# board.net
KiCad netlist of a schematic drawn in EAGLE
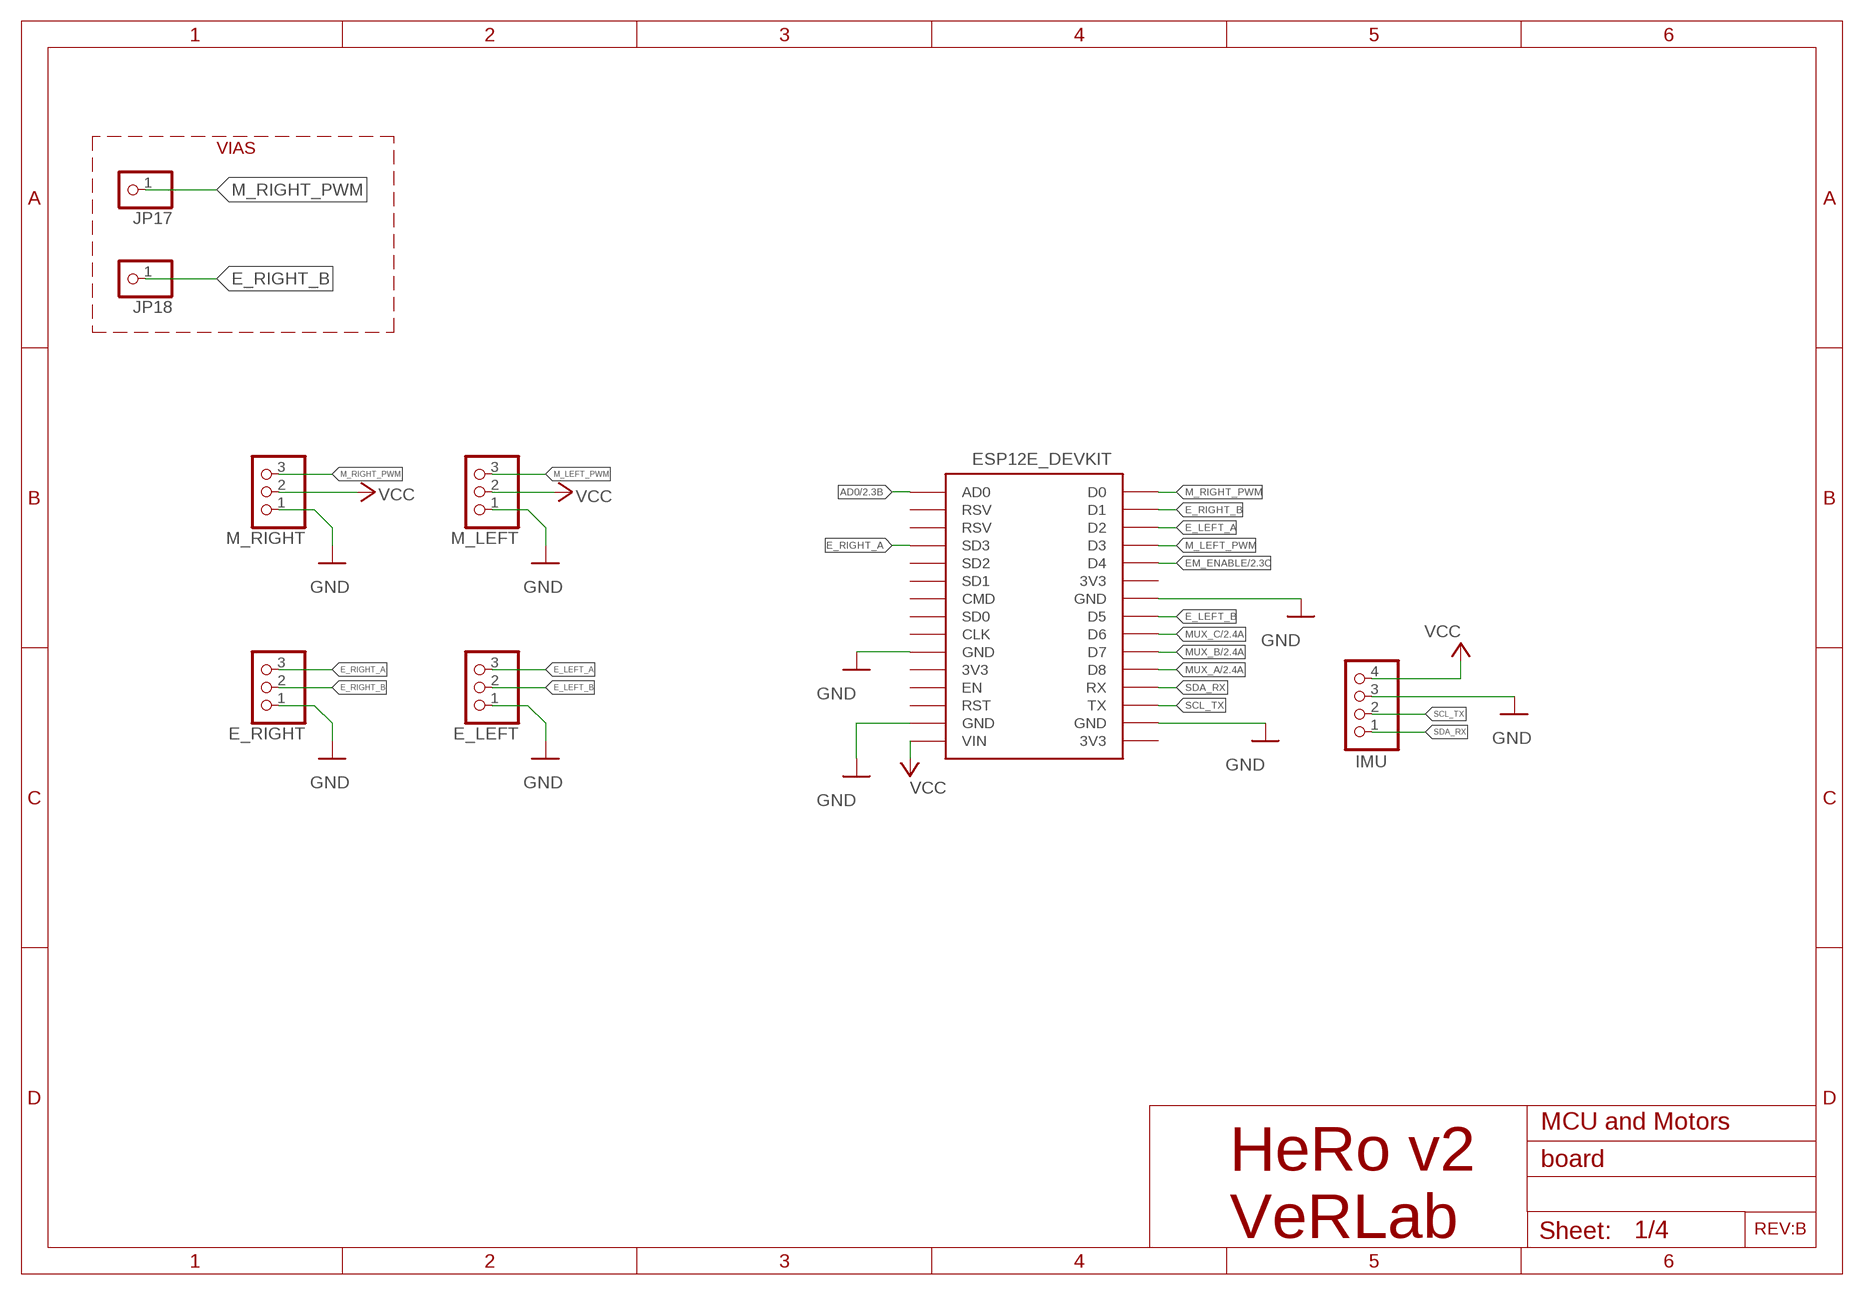
[diagram p0: schematic, sheet 1]
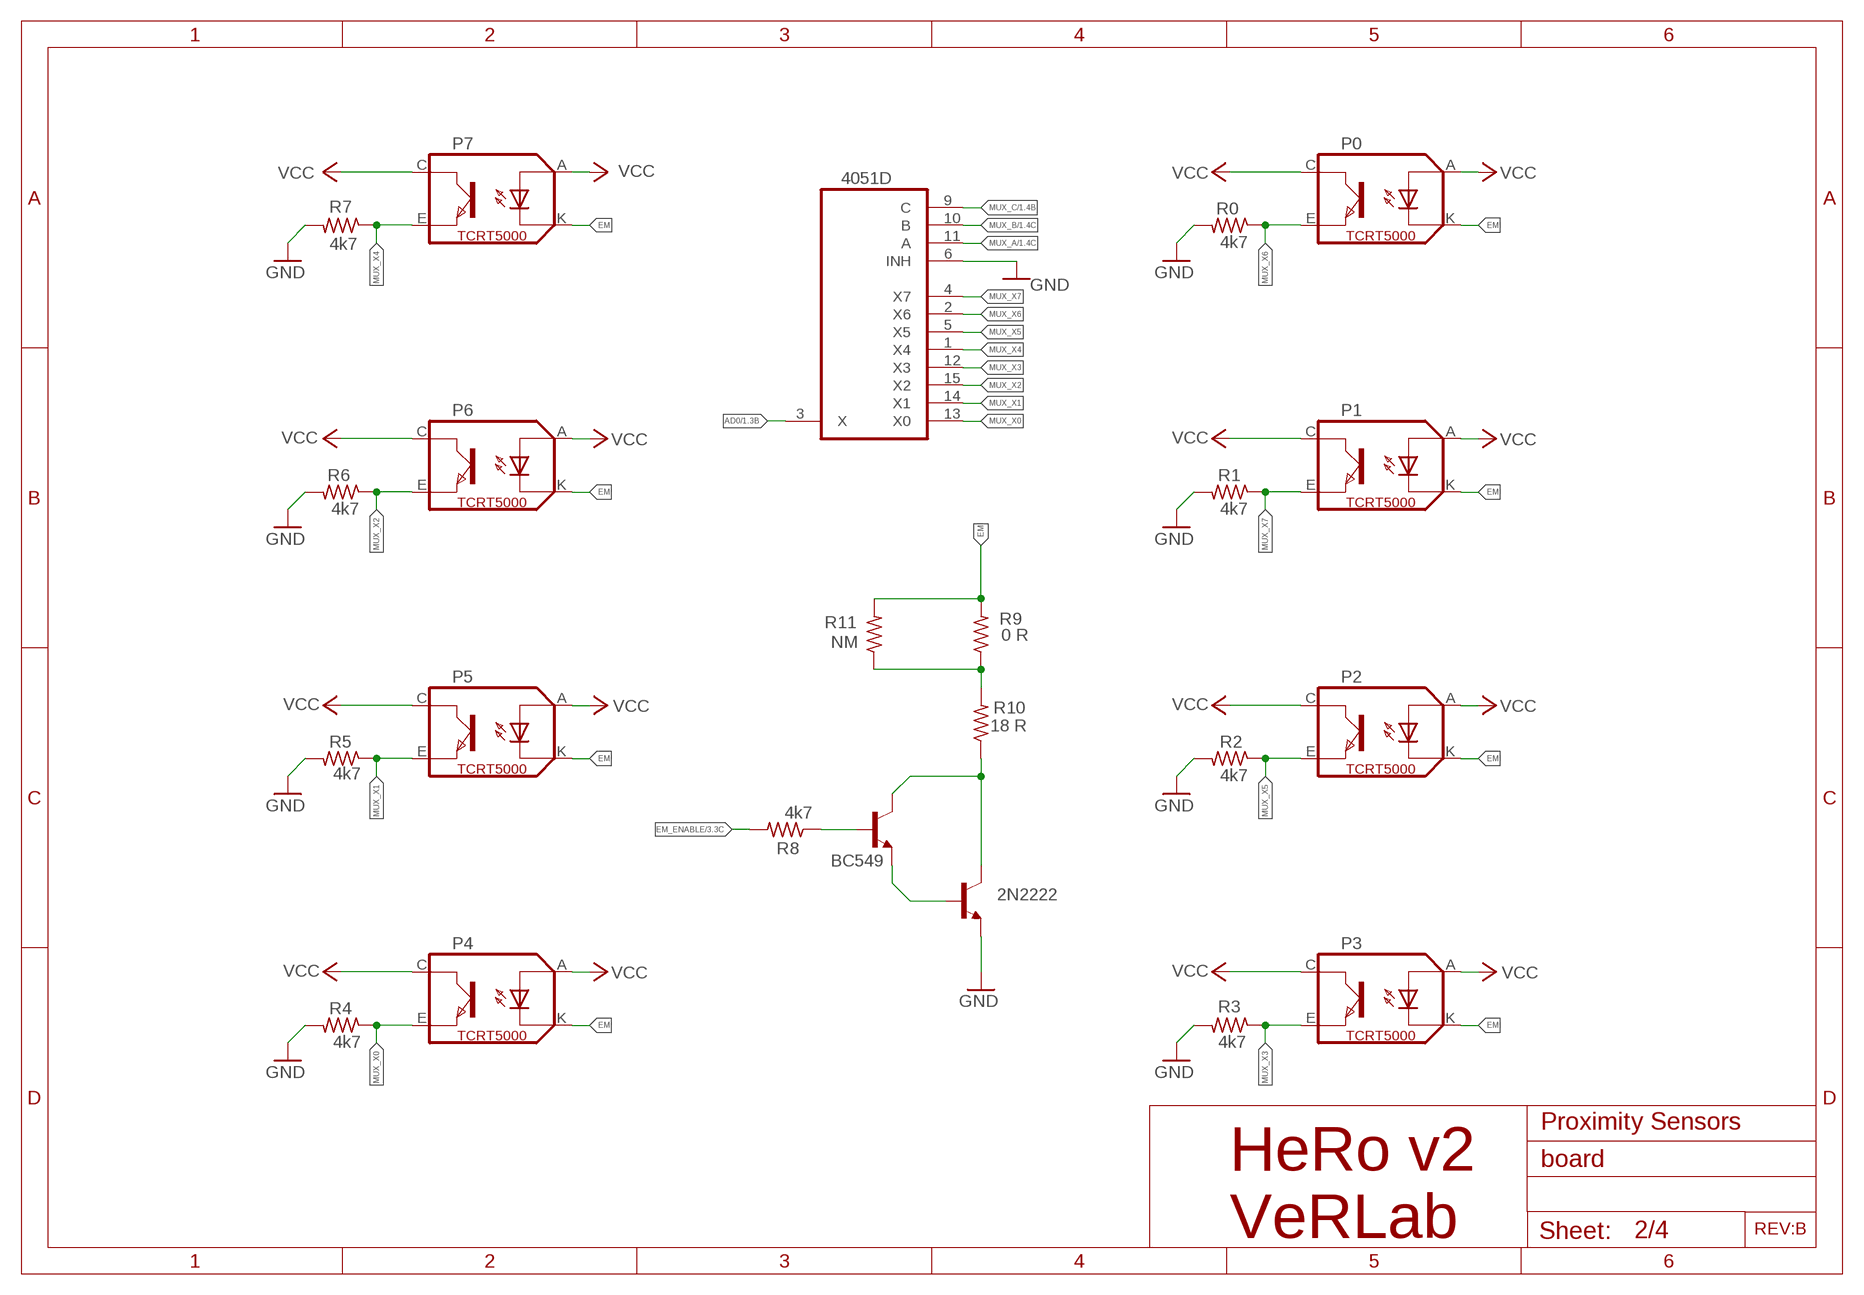
[diagram p1: schematic, sheet 2]
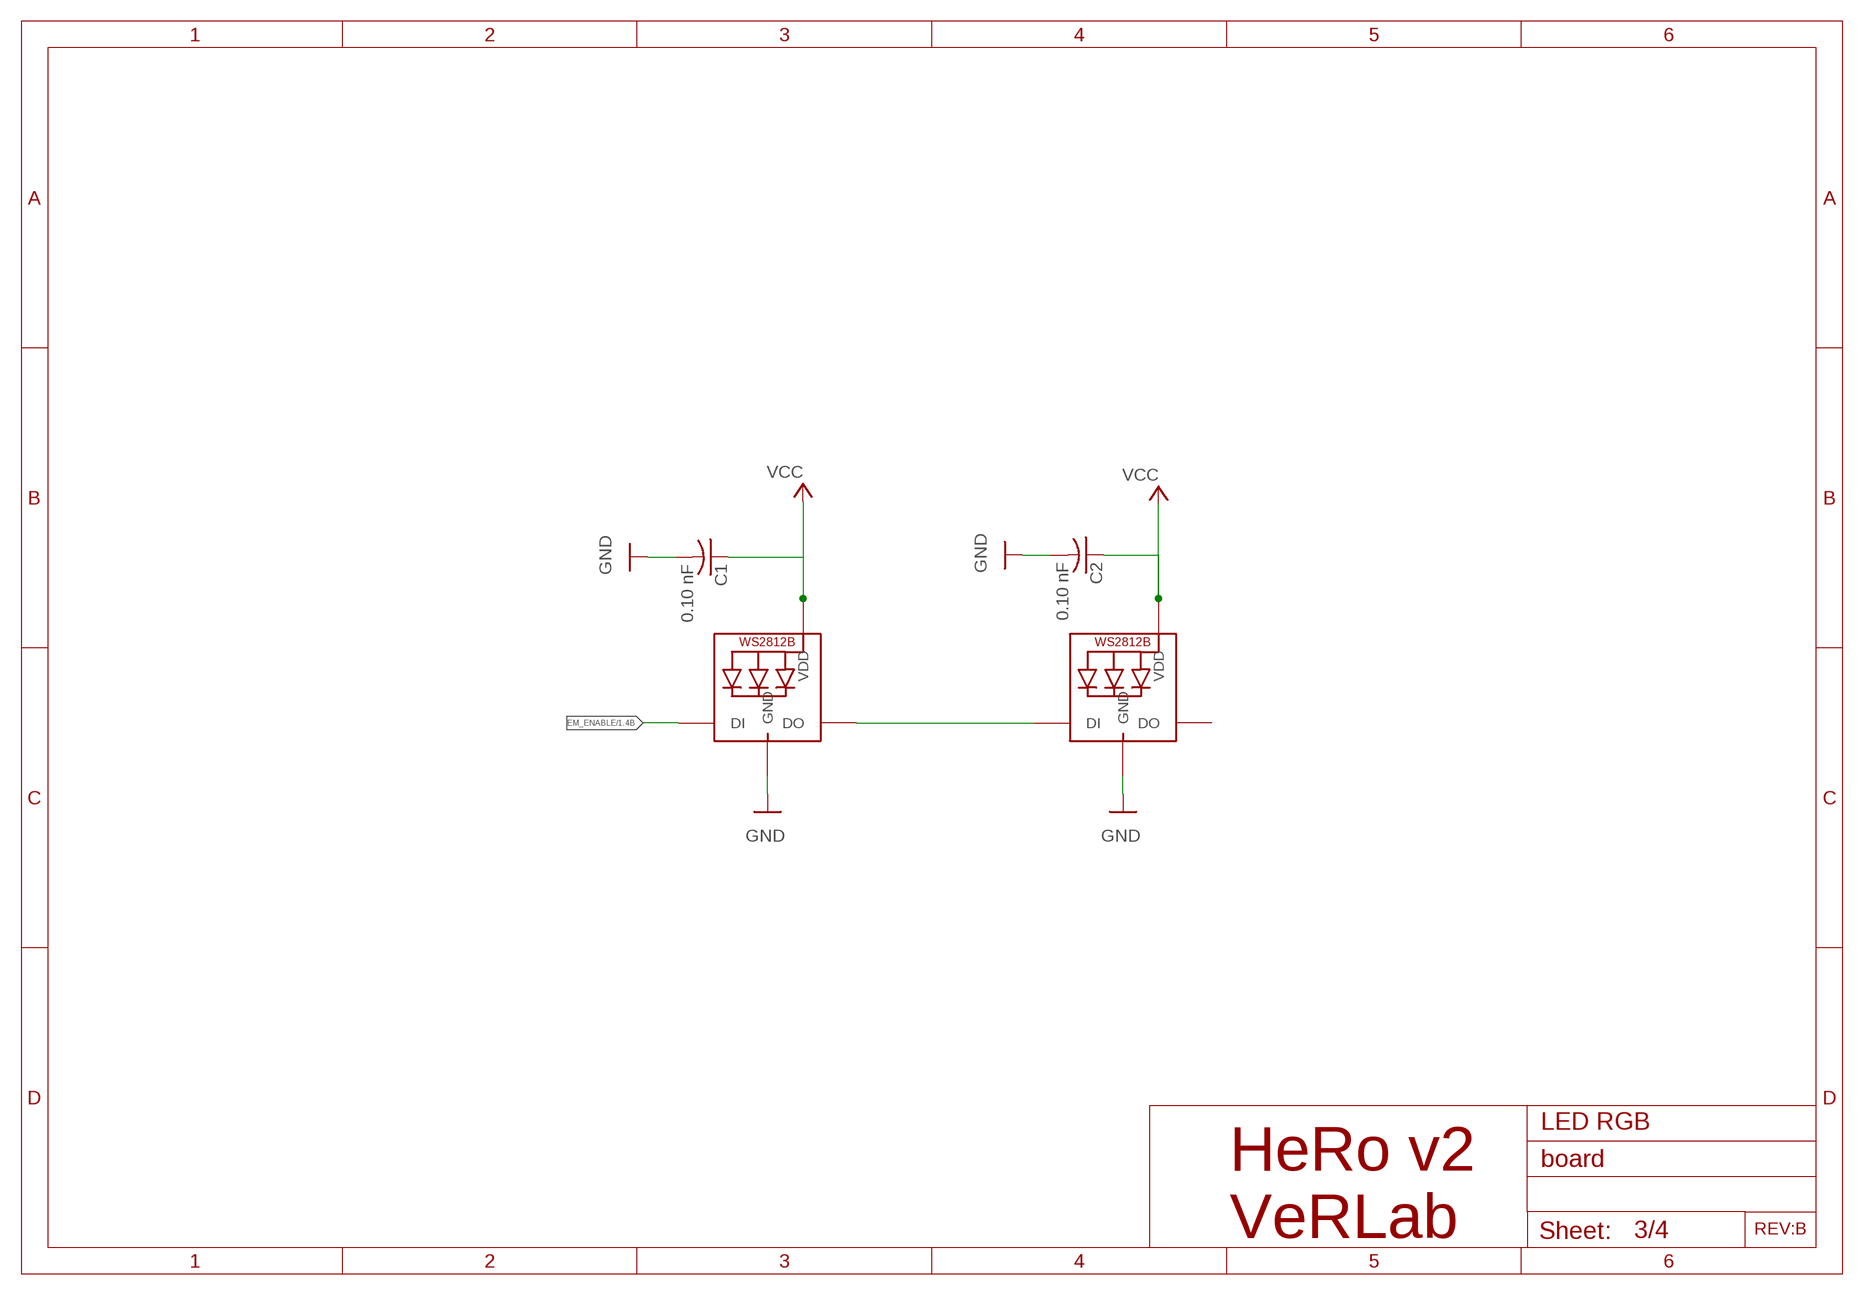
[diagram p2: schematic, sheet 3]
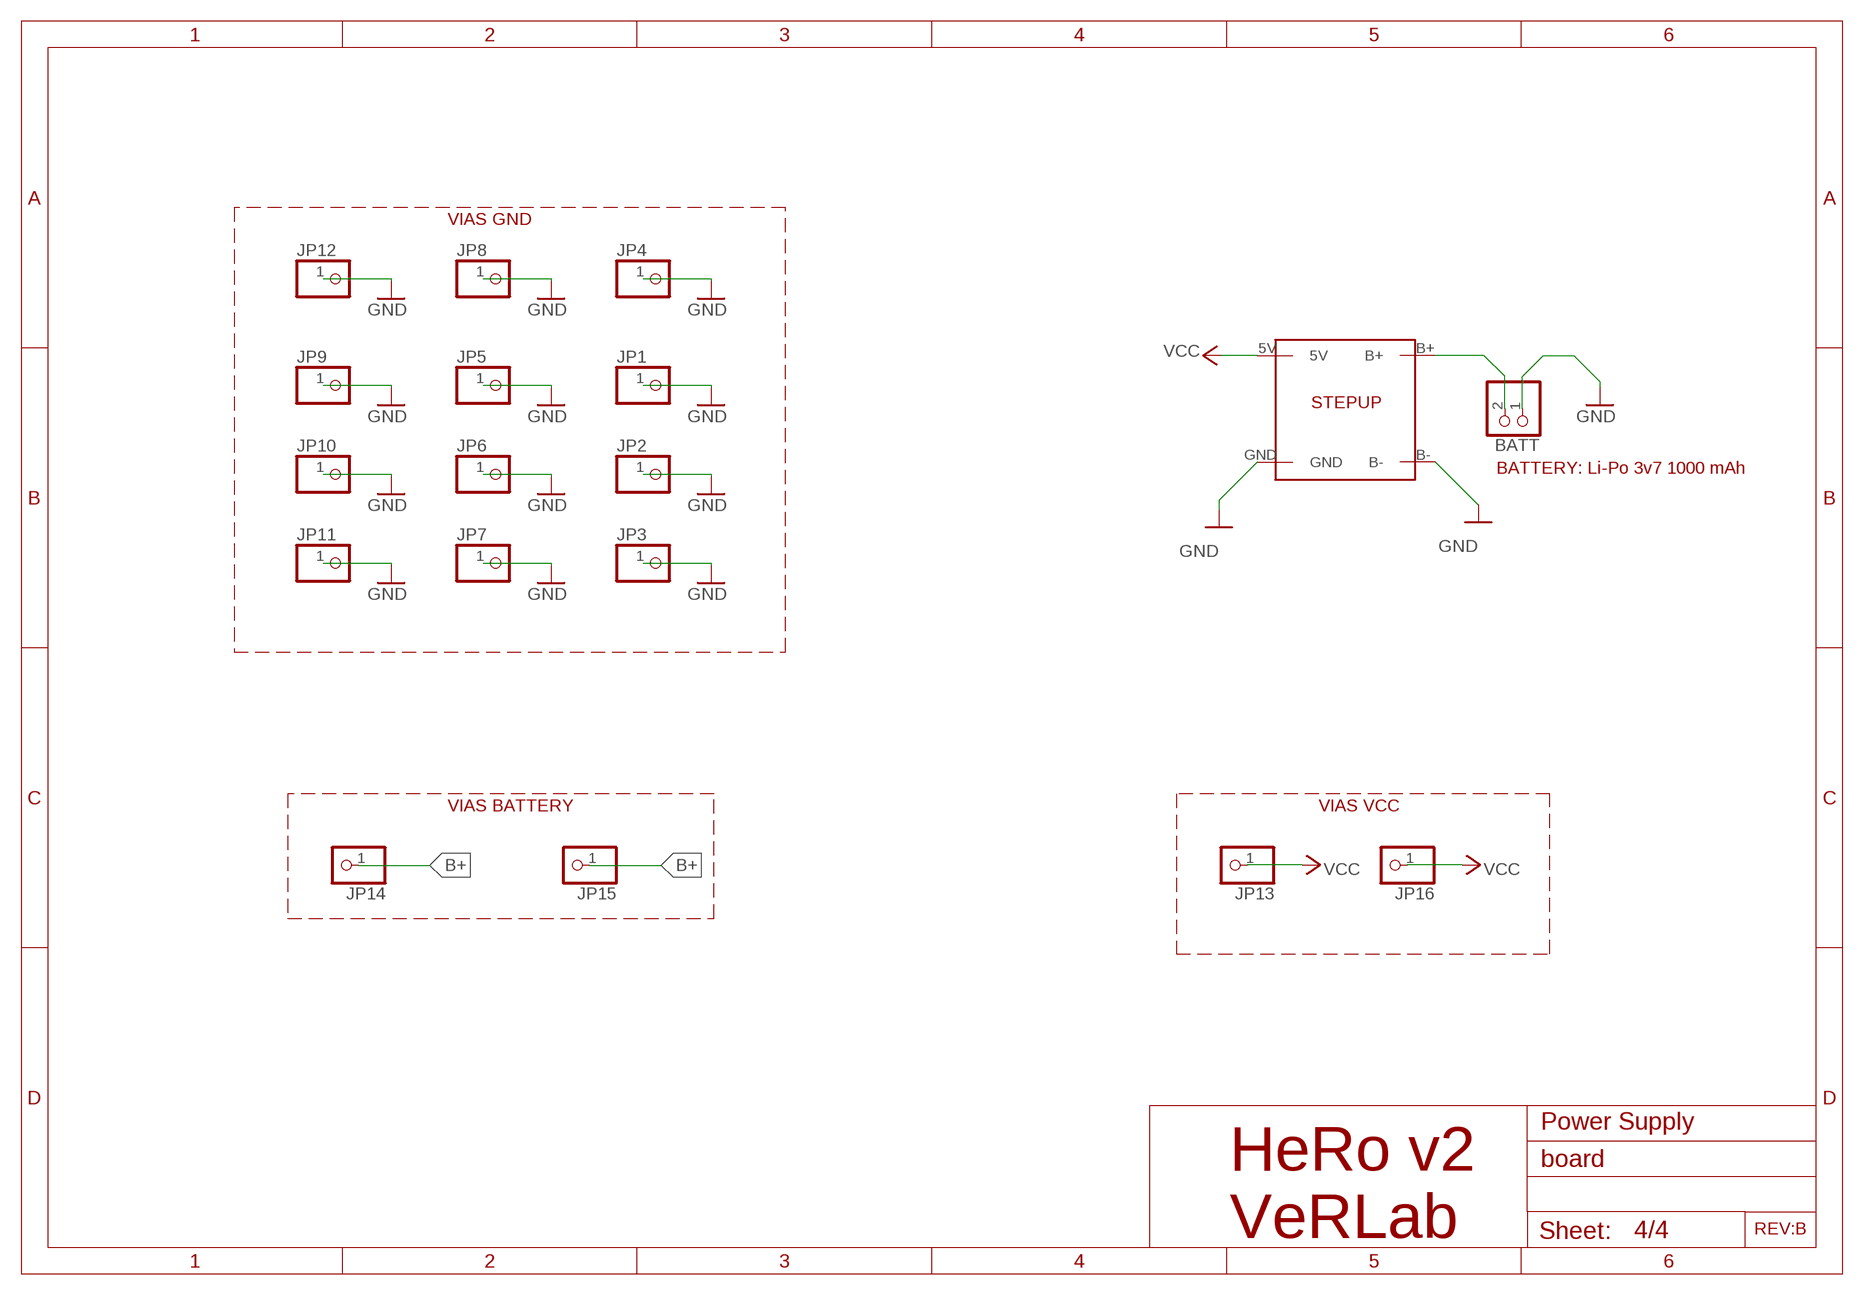
[diagram p3: schematic, sheet 4]

(export (version "E")
  (design (tool "Eeschema 10.0.6"))
  (components
    (comp (ref "C1")
      (value "0.10 nF")
      (footprint "eagle-import:C0603")
      (libsource (lib "eagle-import") (part "C-USC0603"))
    )
    (comp (ref "C2")
      (value "0.10 nF")
      (footprint "eagle-import:C0603")
      (libsource (lib "eagle-import") (part "C-USC0603"))
    )
    (comp (ref "LED3")
      (value "WS2812B5050")
      (footprint "eagle-import:WS2812B")
      (libsource (lib "eagle-import") (part "WS2812B5050"))
    )
    (comp (ref "LED4")
      (value "WS2812B5050")
      (footprint "eagle-import:WS2812B")
      (libsource (lib "eagle-import") (part "WS2812B5050"))
    )
    (comp (ref "E_LEFT")
      (value "PINHD-1X3")
      (footprint "eagle-import:1X03")
      (libsource (lib "eagle-import") (part "PINHD-1X3"))
    )
    (comp (ref "E_RIGHT")
      (value "PINHD-1X3")
      (footprint "eagle-import:1X03")
      (libsource (lib "eagle-import") (part "PINHD-1X3"))
    )
    (comp (ref "IMU")
      (value "PINHD-1X4")
      (footprint "eagle-import:1X04")
      (libsource (lib "eagle-import") (part "PINHD-1X4"))
    )
    (comp (ref "JP17")
      (value "PINHD-1X1")
      (footprint "eagle-import:1X01")
      (libsource (lib "eagle-import") (part "PINHD-1X1"))
    )
    (comp (ref "JP18")
      (value "PINHD-1X1")
      (footprint "eagle-import:1X01")
      (libsource (lib "eagle-import") (part "PINHD-1X1"))
    )
    (comp (ref "M_LEFT")
      (value "PINHD-1X3")
      (footprint "eagle-import:1X03")
      (libsource (lib "eagle-import") (part "PINHD-1X3"))
    )
    (comp (ref "M_RIGHT")
      (value "PINHD-1X3")
      (footprint "eagle-import:1X03")
      (libsource (lib "eagle-import") (part "PINHD-1X3"))
    )
    (comp (ref "U$1")
      (value "ESP12E_DEVKIT")
      (footprint "eagle-import:ESP12E_DEVKIT")
      (libsource (lib "eagle-import") (part "ESP12E_DEVKIT"))
    )
    (comp (ref "BC549")
      (value "BC549-NPN-TO92-CBE")
      (footprint "eagle-import:TO92-CBE")
      (fields (field (name "SPICEPREFIX") "J"))
      (libsource (lib "eagle-import") (part "-NPN-TO92-CBEBC549"))
    )
    (comp (ref "IC2")
      (value "4051D")
      (footprint "eagle-import:SO16")
      (libsource (lib "eagle-import") (part "4051D"))
    )
    (comp (ref "P0")
      (value "TCRT5000")
      (footprint "eagle-import:TCRT5000")
      (libsource (lib "eagle-import") (part "TCRT5000"))
    )
    (comp (ref "P1")
      (value "TCRT5000")
      (footprint "eagle-import:TCRT5000")
      (libsource (lib "eagle-import") (part "TCRT5000"))
    )
    (comp (ref "P2")
      (value "TCRT5000")
      (footprint "eagle-import:TCRT5000")
      (libsource (lib "eagle-import") (part "TCRT5000"))
    )
    (comp (ref "P3")
      (value "TCRT5000")
      (footprint "eagle-import:TCRT5000")
      (libsource (lib "eagle-import") (part "TCRT5000"))
    )
    (comp (ref "P4")
      (value "TCRT5000")
      (footprint "eagle-import:TCRT5000")
      (libsource (lib "eagle-import") (part "TCRT5000"))
    )
    (comp (ref "P5")
      (value "TCRT5000")
      (footprint "eagle-import:TCRT5000")
      (libsource (lib "eagle-import") (part "TCRT5000"))
    )
    (comp (ref "P6")
      (value "TCRT5000")
      (footprint "eagle-import:TCRT5000")
      (libsource (lib "eagle-import") (part "TCRT5000"))
    )
    (comp (ref "P7")
      (value "TCRT5000")
      (footprint "eagle-import:TCRT5000")
      (libsource (lib "eagle-import") (part "TCRT5000"))
    )
    (comp (ref "R0")
      (value "4k7")
      (footprint "eagle-import:M0805")
      (libsource (lib "eagle-import") (part "R-US_M0805"))
    )
    (comp (ref "R1")
      (value "4k7")
      (footprint "eagle-import:M0805")
      (libsource (lib "eagle-import") (part "R-US_M0805"))
    )
    (comp (ref "R2")
      (value "4k7")
      (footprint "eagle-import:M0805")
      (libsource (lib "eagle-import") (part "R-US_M0805"))
    )
    (comp (ref "R3")
      (value "4k7")
      (footprint "eagle-import:M0805")
      (libsource (lib "eagle-import") (part "R-US_M0805"))
    )
    (comp (ref "R4")
      (value "4k7")
      (footprint "eagle-import:M0805")
      (libsource (lib "eagle-import") (part "R-US_M0805"))
    )
    (comp (ref "R5")
      (value "4k7")
      (footprint "eagle-import:M0805")
      (libsource (lib "eagle-import") (part "R-US_M0805"))
    )
    (comp (ref "R6")
      (value "4k7")
      (footprint "eagle-import:M0805")
      (libsource (lib "eagle-import") (part "R-US_M0805"))
    )
    (comp (ref "R7")
      (value "4k7")
      (footprint "eagle-import:M0805")
      (libsource (lib "eagle-import") (part "R-US_M0805"))
    )
    (comp (ref "R8")
      (value "4k7")
      (footprint "eagle-import:R0805")
      (fields (field (name "SPICEPREFIX") "R"))
      (libsource (lib "eagle-import") (part "resistor_348_R-US_R0805"))
    )
    (comp (ref "R9")
      (value "0 R")
      (footprint "eagle-import:R0805")
      (fields (field (name "SPICEPREFIX") "R"))
      (libsource (lib "eagle-import") (part "resistor_348_R-US_R0805"))
    )
    (comp (ref "R10")
      (value "18 R")
      (footprint "eagle-import:R0805")
      (fields (field (name "SPICEPREFIX") "R"))
      (libsource (lib "eagle-import") (part "resistor_348_R-US_R0805"))
    )
    (comp (ref "R11")
      (value "NM")
      (footprint "eagle-import:R0805")
      (fields (field (name "SPICEPREFIX") "R"))
      (libsource (lib "eagle-import") (part "resistor_348_R-US_R0805"))
    )
    (comp (ref "T5")
      (value "2N2222")
      (footprint "eagle-import:TO92-EBC-OVAL")
      (fields (field (name "SPICEPREFIX") "J"))
      (libsource (lib "eagle-import") (part "2N2222"))
    )
    (comp (ref "BATT")
      (value "PINHD-1X2")
      (footprint "eagle-import:1X02")
      (libsource (lib "eagle-import") (part "PINHD-1X2"))
    )
    (comp (ref "JP1")
      (value "PINHD-1X1")
      (footprint "eagle-import:1X01")
      (libsource (lib "eagle-import") (part "PINHD-1X1"))
    )
    (comp (ref "JP2")
      (value "PINHD-1X1")
      (footprint "eagle-import:1X01")
      (libsource (lib "eagle-import") (part "PINHD-1X1"))
    )
    (comp (ref "JP3")
      (value "PINHD-1X1")
      (footprint "eagle-import:1X01")
      (libsource (lib "eagle-import") (part "PINHD-1X1"))
    )
    (comp (ref "JP4")
      (value "PINHD-1X1")
      (footprint "eagle-import:1X01")
      (libsource (lib "eagle-import") (part "PINHD-1X1"))
    )
    (comp (ref "JP5")
      (value "PINHD-1X1")
      (footprint "eagle-import:1X01")
      (libsource (lib "eagle-import") (part "PINHD-1X1"))
    )
    (comp (ref "JP6")
      (value "PINHD-1X1")
      (footprint "eagle-import:1X01")
      (libsource (lib "eagle-import") (part "PINHD-1X1"))
    )
    (comp (ref "JP7")
      (value "PINHD-1X1")
      (footprint "eagle-import:1X01")
      (libsource (lib "eagle-import") (part "PINHD-1X1"))
    )
    (comp (ref "JP8")
      (value "PINHD-1X1")
      (footprint "eagle-import:1X01")
      (libsource (lib "eagle-import") (part "PINHD-1X1"))
    )
    (comp (ref "JP9")
      (value "PINHD-1X1")
      (footprint "eagle-import:1X01")
      (libsource (lib "eagle-import") (part "PINHD-1X1"))
    )
    (comp (ref "JP10")
      (value "PINHD-1X1")
      (footprint "eagle-import:1X01")
      (libsource (lib "eagle-import") (part "PINHD-1X1"))
    )
    (comp (ref "JP11")
      (value "PINHD-1X1")
      (footprint "eagle-import:1X01")
      (libsource (lib "eagle-import") (part "PINHD-1X1"))
    )
    (comp (ref "JP12")
      (value "PINHD-1X1")
      (footprint "eagle-import:1X01")
      (libsource (lib "eagle-import") (part "PINHD-1X1"))
    )
    (comp (ref "JP13")
      (value "PINHD-1X1")
      (footprint "eagle-import:1X01")
      (libsource (lib "eagle-import") (part "PINHD-1X1"))
    )
    (comp (ref "JP14")
      (value "PINHD-1X1")
      (footprint "eagle-import:1X01")
      (libsource (lib "eagle-import") (part "PINHD-1X1"))
    )
    (comp (ref "JP15")
      (value "PINHD-1X1")
      (footprint "eagle-import:1X01")
      (libsource (lib "eagle-import") (part "PINHD-1X1"))
    )
    (comp (ref "JP16")
      (value "PINHD-1X1")
      (footprint "eagle-import:1X01")
      (libsource (lib "eagle-import") (part "PINHD-1X1"))
    )
    (comp (ref "OS1")
      (value "STEPUP")
      (footprint "eagle-import:STEPUP")
      (libsource (lib "eagle-import") (part "STEPUP"))
    )
  )
  (nets
    (net (code "1") (name "AD0") (class "Default")
      (node (ref "IC2") (pin "3") (pinfunction "X_3") (pintype "bidirectional"))
      (node (ref "U$1") (pin "AD0") (pinfunction "AD0_AD0") (pintype "bidirectional"))
    )
    (net (code "2") (name "B+") (class "Default")
      (node (ref "BATT") (pin "2") (pinfunction "2_2") (pintype "passive"))
      (node (ref "JP14") (pin "1") (pinfunction "1_1") (pintype "passive"))
      (node (ref "JP15") (pin "1") (pinfunction "1_1") (pintype "passive"))
      (node (ref "OS1") (pin "B+") (pinfunction "B+_B+") (pintype "input"))
    )
    (net (code "3") (name "EM") (class "Default")
      (node (ref "P0") (pin "K") (pinfunction "CATHODE_K") (pintype "passive"))
      (node (ref "P1") (pin "K") (pinfunction "CATHODE_K") (pintype "passive"))
      (node (ref "P2") (pin "K") (pinfunction "CATHODE_K") (pintype "passive"))
      (node (ref "P3") (pin "K") (pinfunction "CATHODE_K") (pintype "passive"))
      (node (ref "P4") (pin "K") (pinfunction "CATHODE_K") (pintype "passive"))
      (node (ref "P5") (pin "K") (pinfunction "CATHODE_K") (pintype "passive"))
      (node (ref "P6") (pin "K") (pinfunction "CATHODE_K") (pintype "passive"))
      (node (ref "P7") (pin "K") (pinfunction "CATHODE_K") (pintype "passive"))
      (node (ref "R11") (pin "2") (pinfunction "2_2") (pintype "passive"))
      (node (ref "R9") (pin "2") (pinfunction "2_2") (pintype "passive"))
    )
    (net (code "4") (name "EM_ENABLE") (class "Default")
      (node (ref "LED3") (pin "4-DIN") (pinfunction "DI_4-DIN") (pintype "input"))
      (node (ref "R8") (pin "2") (pinfunction "2_2") (pintype "passive"))
      (node (ref "U$1") (pin "D4") (pinfunction "D4_D4") (pintype "bidirectional"))
    )
    (net (code "5") (name "E_LEFT_A") (class "Default")
      (node (ref "E_LEFT") (pin "3") (pinfunction "3_3") (pintype "passive"))
      (node (ref "U$1") (pin "D2") (pinfunction "D2_D2") (pintype "bidirectional"))
    )
    (net (code "6") (name "E_LEFT_B") (class "Default")
      (node (ref "E_LEFT") (pin "2") (pinfunction "2_2") (pintype "passive"))
      (node (ref "U$1") (pin "D5") (pinfunction "D5_D5") (pintype "bidirectional"))
    )
    (net (code "7") (name "E_RIGHT_A") (class "Default")
      (node (ref "E_RIGHT") (pin "3") (pinfunction "3_3") (pintype "passive"))
      (node (ref "U$1") (pin "SD3") (pinfunction "SD3_SD3") (pintype "bidirectional"))
    )
    (net (code "8") (name "E_RIGHT_B") (class "Default")
      (node (ref "E_RIGHT") (pin "2") (pinfunction "2_2") (pintype "passive"))
      (node (ref "JP18") (pin "1") (pinfunction "1_1") (pintype "passive"))
      (node (ref "U$1") (pin "D1") (pinfunction "D1_D1") (pintype "bidirectional"))
    )
    (net (code "9") (name "GND") (class "Default")
      (node (ref "BATT") (pin "1") (pinfunction "1_1") (pintype "passive"))
      (node (ref "C1") (pin "2") (pinfunction "2_2") (pintype "passive"))
      (node (ref "C2") (pin "2") (pinfunction "2_2") (pintype "passive"))
      (node (ref "E_LEFT") (pin "1") (pinfunction "1_1") (pintype "passive"))
      (node (ref "E_RIGHT") (pin "1") (pinfunction "1_1") (pintype "passive"))
      (node (ref "IC2") (pin "6") (pinfunction "INH_6") (pintype "input"))
      (node (ref "IMU") (pin "3") (pinfunction "3_3") (pintype "passive"))
      (node (ref "JP1") (pin "1") (pinfunction "1_1") (pintype "passive"))
      (node (ref "JP10") (pin "1") (pinfunction "1_1") (pintype "passive"))
      (node (ref "JP11") (pin "1") (pinfunction "1_1") (pintype "passive"))
      (node (ref "JP12") (pin "1") (pinfunction "1_1") (pintype "passive"))
      (node (ref "JP2") (pin "1") (pinfunction "1_1") (pintype "passive"))
      (node (ref "JP3") (pin "1") (pinfunction "1_1") (pintype "passive"))
      (node (ref "JP4") (pin "1") (pinfunction "1_1") (pintype "passive"))
      (node (ref "JP5") (pin "1") (pinfunction "1_1") (pintype "passive"))
      (node (ref "JP6") (pin "1") (pinfunction "1_1") (pintype "passive"))
      (node (ref "JP7") (pin "1") (pinfunction "1_1") (pintype "passive"))
      (node (ref "JP8") (pin "1") (pinfunction "1_1") (pintype "passive"))
      (node (ref "JP9") (pin "1") (pinfunction "1_1") (pintype "passive"))
      (node (ref "LED3") (pin "3-GND") (pinfunction "GND_3-GND") (pintype "power_in"))
      (node (ref "LED4") (pin "3-GND") (pinfunction "GND_3-GND") (pintype "power_in"))
      (node (ref "M_LEFT") (pin "1") (pinfunction "1_1") (pintype "passive"))
      (node (ref "M_RIGHT") (pin "1") (pinfunction "1_1") (pintype "passive"))
      (node (ref "OS1") (pin "B-") (pinfunction "B-_B-") (pintype "input"))
      (node (ref "OS1") (pin "GND") (pinfunction "GND_GND") (pintype "output"))
      (node (ref "R0") (pin "2") (pinfunction "2_2") (pintype "passive"))
      (node (ref "R1") (pin "2") (pinfunction "2_2") (pintype "passive"))
      (node (ref "R2") (pin "2") (pinfunction "2_2") (pintype "passive"))
      (node (ref "R3") (pin "2") (pinfunction "2_2") (pintype "passive"))
      (node (ref "R4") (pin "2") (pinfunction "2_2") (pintype "passive"))
      (node (ref "R5") (pin "2") (pinfunction "2_2") (pintype "passive"))
      (node (ref "R6") (pin "2") (pinfunction "2_2") (pintype "passive"))
      (node (ref "R7") (pin "2") (pinfunction "2_2") (pintype "passive"))
      (node (ref "T5") (pin "E") (pinfunction "E_E") (pintype "passive"))
      (node (ref "U$1") (pin "GND@0") (pinfunction "GND_GND@0") (pintype "bidirectional"))
      (node (ref "U$1") (pin "GND@1") (pinfunction "GND_GND@1") (pintype "bidirectional"))
      (node (ref "U$1") (pin "GND@2") (pinfunction "GND_GND@2") (pintype "bidirectional"))
      (node (ref "U$1") (pin "GND@3") (pinfunction "GND_GND@3") (pintype "bidirectional"))
    )
    (net (code "10") (name "MUX_A") (class "Default")
      (node (ref "IC2") (pin "11") (pinfunction "A_11") (pintype "input"))
      (node (ref "U$1") (pin "D8") (pinfunction "D8_D8") (pintype "bidirectional"))
    )
    (net (code "11") (name "MUX_B") (class "Default")
      (node (ref "IC2") (pin "10") (pinfunction "B_10") (pintype "input"))
      (node (ref "U$1") (pin "D7") (pinfunction "D7_D7") (pintype "bidirectional"))
    )
    (net (code "12") (name "MUX_C") (class "Default")
      (node (ref "IC2") (pin "9") (pinfunction "C_9") (pintype "input"))
      (node (ref "U$1") (pin "D6") (pinfunction "D6_D6") (pintype "bidirectional"))
    )
    (net (code "13") (name "MUX_X0") (class "Default")
      (node (ref "IC2") (pin "13") (pinfunction "X0_13") (pintype "bidirectional"))
      (node (ref "P4") (pin "E") (pinfunction "EMITTER_E") (pintype "passive"))
      (node (ref "R4") (pin "1") (pinfunction "1_1") (pintype "passive"))
    )
    (net (code "14") (name "MUX_X1") (class "Default")
      (node (ref "IC2") (pin "14") (pinfunction "X1_14") (pintype "bidirectional"))
      (node (ref "P5") (pin "E") (pinfunction "EMITTER_E") (pintype "passive"))
      (node (ref "R5") (pin "1") (pinfunction "1_1") (pintype "passive"))
    )
    (net (code "15") (name "MUX_X2") (class "Default")
      (node (ref "IC2") (pin "15") (pinfunction "X2_15") (pintype "bidirectional"))
      (node (ref "P6") (pin "E") (pinfunction "EMITTER_E") (pintype "passive"))
      (node (ref "R6") (pin "1") (pinfunction "1_1") (pintype "passive"))
    )
    (net (code "16") (name "MUX_X3") (class "Default")
      (node (ref "IC2") (pin "12") (pinfunction "X3_12") (pintype "bidirectional"))
      (node (ref "P3") (pin "E") (pinfunction "EMITTER_E") (pintype "passive"))
      (node (ref "R3") (pin "1") (pinfunction "1_1") (pintype "passive"))
    )
    (net (code "17") (name "MUX_X4") (class "Default")
      (node (ref "IC2") (pin "1") (pinfunction "X4_1") (pintype "bidirectional"))
      (node (ref "P7") (pin "E") (pinfunction "EMITTER_E") (pintype "passive"))
      (node (ref "R7") (pin "1") (pinfunction "1_1") (pintype "passive"))
    )
    (net (code "18") (name "MUX_X5") (class "Default")
      (node (ref "IC2") (pin "5") (pinfunction "X5_5") (pintype "bidirectional"))
      (node (ref "P2") (pin "E") (pinfunction "EMITTER_E") (pintype "passive"))
      (node (ref "R2") (pin "1") (pinfunction "1_1") (pintype "passive"))
    )
    (net (code "19") (name "MUX_X6") (class "Default")
      (node (ref "IC2") (pin "2") (pinfunction "X6_2") (pintype "bidirectional"))
      (node (ref "P0") (pin "E") (pinfunction "EMITTER_E") (pintype "passive"))
      (node (ref "R0") (pin "1") (pinfunction "1_1") (pintype "passive"))
    )
    (net (code "20") (name "MUX_X7") (class "Default")
      (node (ref "IC2") (pin "4") (pinfunction "X7_4") (pintype "bidirectional"))
      (node (ref "P1") (pin "E") (pinfunction "EMITTER_E") (pintype "passive"))
      (node (ref "R1") (pin "1") (pinfunction "1_1") (pintype "passive"))
    )
    (net (code "21") (name "M_LEFT_PWM") (class "Default")
      (node (ref "M_LEFT") (pin "3") (pinfunction "3_3") (pintype "passive"))
      (node (ref "U$1") (pin "D3") (pinfunction "D3_D3") (pintype "bidirectional"))
    )
    (net (code "22") (name "M_RIGHT_PWM") (class "Default")
      (node (ref "JP17") (pin "1") (pinfunction "1_1") (pintype "passive"))
      (node (ref "M_RIGHT") (pin "3") (pinfunction "3_3") (pintype "passive"))
      (node (ref "U$1") (pin "D0") (pinfunction "D0_D0") (pintype "bidirectional"))
    )
    (net (code "23") (name "Net-(BC549-PadB)") (class "Default")
      (node (ref "BC549") (pin "B") (pinfunction "B_B") (pintype "passive"))
      (node (ref "R8") (pin "1") (pinfunction "1_1") (pintype "passive"))
    )
    (net (code "24") (name "Net-(BC549-PadC)") (class "Default")
      (node (ref "BC549") (pin "C") (pinfunction "C_C") (pintype "passive"))
      (node (ref "R10") (pin "1") (pinfunction "1_1") (pintype "passive"))
      (node (ref "T5") (pin "C") (pinfunction "C_C") (pintype "passive"))
    )
    (net (code "25") (name "Net-(BC549-PadE)") (class "Default")
      (node (ref "BC549") (pin "E") (pinfunction "E_E") (pintype "passive"))
      (node (ref "T5") (pin "B") (pinfunction "B_B") (pintype "passive"))
    )
    (net (code "26") (name "Net-(LED3-DO)") (class "Default")
      (node (ref "LED3") (pin "2-DOUT") (pinfunction "DO_2-DOUT") (pintype "output"))
      (node (ref "LED4") (pin "4-DIN") (pinfunction "DI_4-DIN") (pintype "input"))
    )
    (net (code "27") (name "Net-(R10-Pad2)") (class "Default")
      (node (ref "R10") (pin "2") (pinfunction "2_2") (pintype "passive"))
      (node (ref "R11") (pin "1") (pinfunction "1_1") (pintype "passive"))
      (node (ref "R9") (pin "1") (pinfunction "1_1") (pintype "passive"))
    )
    (net (code "28") (name "SCL_TX") (class "Default")
      (node (ref "IMU") (pin "2") (pinfunction "2_2") (pintype "passive"))
      (node (ref "U$1") (pin "TX") (pinfunction "TX_TX") (pintype "bidirectional"))
    )
    (net (code "29") (name "SDA_RX") (class "Default")
      (node (ref "IMU") (pin "1") (pinfunction "1_1") (pintype "passive"))
      (node (ref "U$1") (pin "RX") (pinfunction "RX_RX") (pintype "bidirectional"))
    )
    (net (code "30") (name "VCC") (class "Default")
      (node (ref "C1") (pin "1") (pinfunction "1_1") (pintype "passive"))
      (node (ref "C2") (pin "1") (pinfunction "1_1") (pintype "passive"))
      (node (ref "IMU") (pin "4") (pinfunction "4_4") (pintype "passive"))
      (node (ref "JP13") (pin "1") (pinfunction "1_1") (pintype "passive"))
      (node (ref "JP16") (pin "1") (pinfunction "1_1") (pintype "passive"))
      (node (ref "LED3") (pin "1-VDD") (pinfunction "VDD_1-VDD") (pintype "power_in"))
      (node (ref "LED4") (pin "1-VDD") (pinfunction "VDD_1-VDD") (pintype "power_in"))
      (node (ref "M_LEFT") (pin "2") (pinfunction "2_2") (pintype "passive"))
      (node (ref "M_RIGHT") (pin "2") (pinfunction "2_2") (pintype "passive"))
      (node (ref "OS1") (pin "5V") (pinfunction "5V_5V") (pintype "output"))
      (node (ref "P0") (pin "A") (pinfunction "ANODE_A") (pintype "passive"))
      (node (ref "P0") (pin "C") (pinfunction "COLLECTOR_C") (pintype "passive"))
      (node (ref "P1") (pin "A") (pinfunction "ANODE_A") (pintype "passive"))
      (node (ref "P1") (pin "C") (pinfunction "COLLECTOR_C") (pintype "passive"))
      (node (ref "P2") (pin "A") (pinfunction "ANODE_A") (pintype "passive"))
      (node (ref "P2") (pin "C") (pinfunction "COLLECTOR_C") (pintype "passive"))
      (node (ref "P3") (pin "A") (pinfunction "ANODE_A") (pintype "passive"))
      (node (ref "P3") (pin "C") (pinfunction "COLLECTOR_C") (pintype "passive"))
      (node (ref "P4") (pin "A") (pinfunction "ANODE_A") (pintype "passive"))
      (node (ref "P4") (pin "C") (pinfunction "COLLECTOR_C") (pintype "passive"))
      (node (ref "P5") (pin "A") (pinfunction "ANODE_A") (pintype "passive"))
      (node (ref "P5") (pin "C") (pinfunction "COLLECTOR_C") (pintype "passive"))
      (node (ref "P6") (pin "A") (pinfunction "ANODE_A") (pintype "passive"))
      (node (ref "P6") (pin "C") (pinfunction "COLLECTOR_C") (pintype "passive"))
      (node (ref "P7") (pin "A") (pinfunction "ANODE_A") (pintype "passive"))
      (node (ref "P7") (pin "C") (pinfunction "COLLECTOR_C") (pintype "passive"))
      (node (ref "U$1") (pin "VIN") (pinfunction "VIN_VIN") (pintype "bidirectional"))
    )
    (net (code "31") (name "unconnected-(LED4-DO-Pad2-DOUT)") (class "Default")
      (node (ref "LED4") (pin "2-DOUT") (pinfunction "DO_2-DOUT") (pintype "output"))
    )
    (net (code "32") (name "unconnected-(U$1-3V3-Pad3V3@0)") (class "Default")
      (node (ref "U$1") (pin "3V3@0") (pinfunction "3V3_3V3@0") (pintype "bidirectional"))
    )
    (net (code "33") (name "unconnected-(U$1-3V3-Pad3V3@1)") (class "Default")
      (node (ref "U$1") (pin "3V3@1") (pinfunction "3V3_3V3@1") (pintype "bidirectional"))
    )
    (net (code "34") (name "unconnected-(U$1-3V3-Pad3V3@2)") (class "Default")
      (node (ref "U$1") (pin "3V3@2") (pinfunction "3V3_3V3@2") (pintype "bidirectional"))
    )
    (net (code "35") (name "unconnected-(U$1-PadCLK)") (class "Default")
      (node (ref "U$1") (pin "CLK") (pinfunction "CLK_CLK") (pintype "bidirectional"))
    )
    (net (code "36") (name "unconnected-(U$1-PadCMD)") (class "Default")
      (node (ref "U$1") (pin "CMD") (pinfunction "CMD_CMD") (pintype "bidirectional"))
    )
    (net (code "37") (name "unconnected-(U$1-PadEN)") (class "Default")
      (node (ref "U$1") (pin "EN") (pinfunction "EN_EN") (pintype "bidirectional"))
    )
    (net (code "38") (name "unconnected-(U$1-PadRST)") (class "Default")
      (node (ref "U$1") (pin "RST") (pinfunction "RST_RST") (pintype "bidirectional"))
    )
    (net (code "39") (name "unconnected-(U$1-PadSD0)") (class "Default")
      (node (ref "U$1") (pin "SD0") (pinfunction "SD0_SD0") (pintype "bidirectional"))
    )
    (net (code "40") (name "unconnected-(U$1-PadSD1)") (class "Default")
      (node (ref "U$1") (pin "SD1") (pinfunction "SD1_SD1") (pintype "bidirectional"))
    )
    (net (code "41") (name "unconnected-(U$1-PadSD2)") (class "Default")
      (node (ref "U$1") (pin "SD2") (pinfunction "SD2_SD2") (pintype "bidirectional"))
    )
    (net (code "42") (name "unconnected-(U$1-RSV-PadRSV@0)") (class "Default")
      (node (ref "U$1") (pin "RSV@0") (pinfunction "RSV_RSV@0") (pintype "bidirectional"))
    )
    (net (code "43") (name "unconnected-(U$1-RSV-PadRSV@1)") (class "Default")
      (node (ref "U$1") (pin "RSV@1") (pinfunction "RSV_RSV@1") (pintype "bidirectional"))
    )
  )
)
